# PowerMngt.net
KiCad netlist of a schematic drawn in Altium Designer
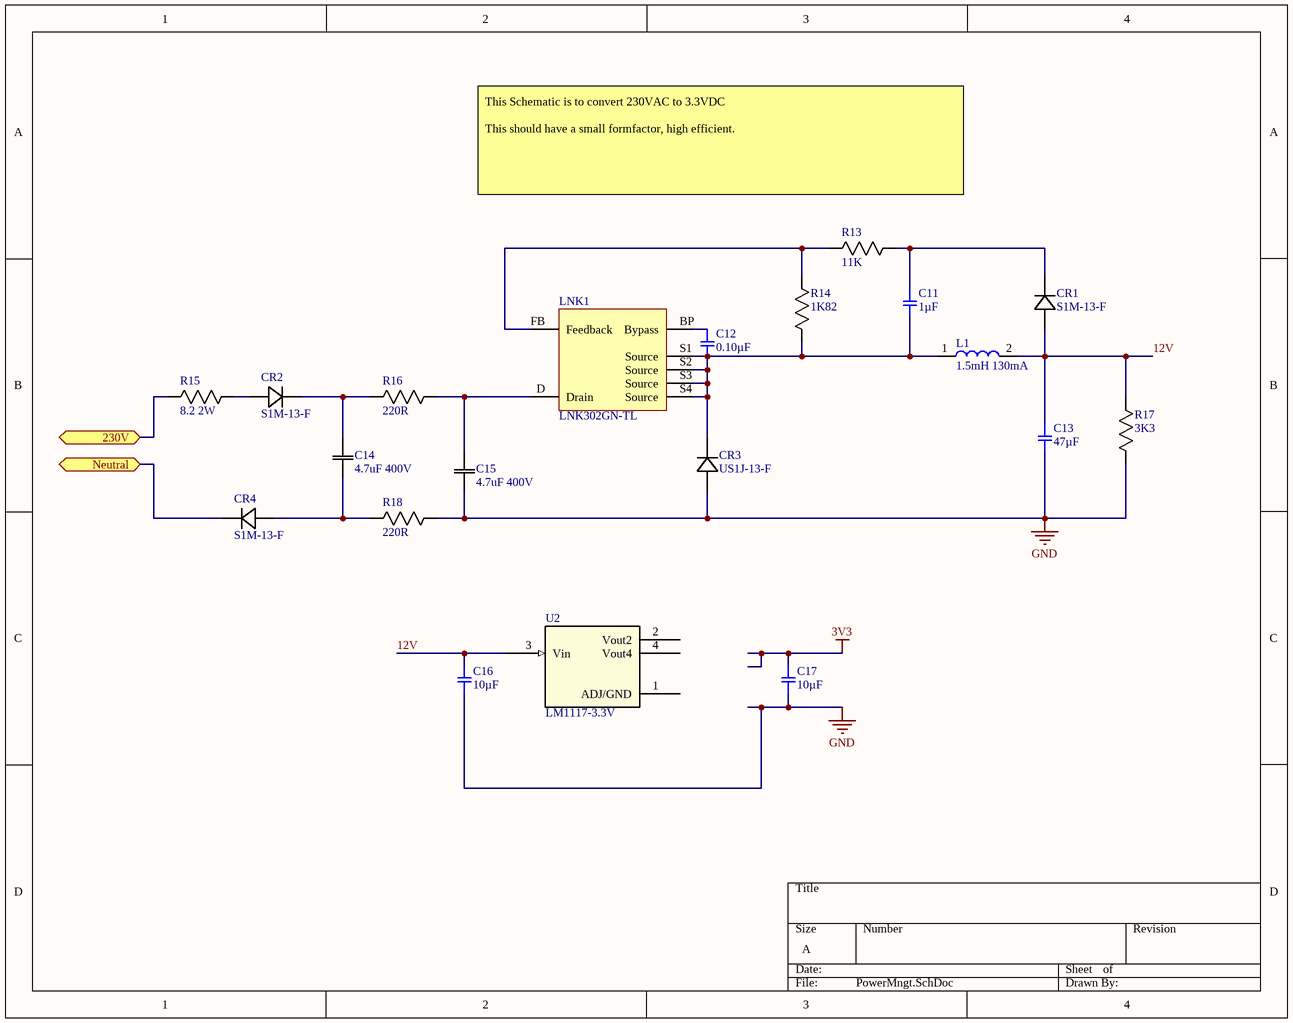
[diagram p0: PowerMngt.SchDoc]

(export (version "E")
  (design (tool "Eeschema 10.0.6"))
  (components
    (comp (ref "C11")
      (value "1µF")
      (footprint "SMD-0603C")
      (description "CAP CER 1UF 16V X5R 0603")
      (fields
        (field (name "DIGI-KEY PART NUMBER") "490-10480-1-ND")
        (field (name "PART NUMBER") "GRM188R61C105MA12D")
      )
      (libsource (lib "Capacitors") (part "GRM188R61C105MA12D"))
    )
    (comp (ref "C12")
      (value "0.10µF")
      (footprint "SMD-0402C")
      (description "CAP CER 0.1UF 16V X7R 0402")
      (fields
        (field (name "DIGI-KEY PART NUMBER") "490-4759-1-ND")
        (field (name "PART NUMBER") "GCM155R71C104KA55D")
      )
      (libsource (lib "Capacitors") (part "GCM155R71C104KA55D"))
    )
    (comp (ref "C13")
      (value "47µF")
      (footprint "SMD-1210C")
      (description "CAP CER 47UF 16V X6S 1210")
      (fields
        (field (name "DIGI-KEY PART NUMBER") "490-10531-1-ND")
        (field (name "PART NUMBER") "GRM32EC81C476KE15L")
      )
      (libsource (lib "Capacitors") (part "GRM32EC81C476KE15L"))
    )
    (comp (ref "C14")
      (value "4.7uF 400V")
      (footprint "CAP_PAN_EEE_G17")
      (description "Imported")
      (fields (field (name "MANUFACTURER_PART_NUMBER") "EEV-EB2G4R7Q"))
      (libsource (lib "XBeeLight") (part "EEV-EB2G4R7Q"))
    )
    (comp (ref "C15")
      (value "4.7uF 400V")
      (footprint "CAP_PAN_EEE_G17")
      (description "Imported")
      (fields (field (name "MANUFACTURER_PART_NUMBER") "EEV-EB2G4R7Q"))
      (libsource (lib "XBeeLight") (part "EEV-EB2G4R7Q"))
    )
    (comp (ref "C16")
      (value "10µF")
      (footprint "SMD-0603C")
      (description "CAP CER 10UF 6.3V X5R 0603")
      (fields
        (field (name "DIGI-KEY PART NUMBER") "490-12538-1-ND")
        (field (name "PART NUMBER") "GRM188R60J106KE47D")
      )
      (libsource (lib "Capacitors") (part "GRM188R60J106KE47D"))
    )
    (comp (ref "C17")
      (value "10µF")
      (footprint "SMD-0603C")
      (description "CAP CER 10UF 6.3V X5R 0603")
      (fields
        (field (name "DIGI-KEY PART NUMBER") "490-12538-1-ND")
        (field (name "PART NUMBER") "GRM188R60J106KE47D")
      )
      (libsource (lib "Capacitors") (part "GRM188R60J106KE47D"))
    )
    (comp (ref "CR1")
      (value "S1M-13-F")
      (footprint "SMA")
      (description "Imported")
      (libsource (lib "XBeeLight") (part "S1M-13-F"))
    )
    (comp (ref "CR2")
      (value "S1M-13-F")
      (footprint "SMA")
      (description "Imported")
      (libsource (lib "XBeeLight") (part "S1M-13-F"))
    )
    (comp (ref "CR3")
      (value "US1J-13-F")
      (footprint "SMA")
      (description "Imported")
      (libsource (lib "XBeeLight") (part "US1J-13-F"))
    )
    (comp (ref "CR4")
      (value "S1M-13-F")
      (footprint "SMA")
      (description "Imported")
      (libsource (lib "XBeeLight") (part "S1M-13-F"))
    )
    (comp (ref "L1")
      (value "1.5mH 130mA")
      (footprint "AIAP-01")
      (description "Imported")
      (fields (field (name "MANUFACTURER_PART_NUMBER") "AIAP-01-152K-T"))
      (libsource (lib "XBeeLight") (part "AIAP-01-152K-T"))
    )
    (comp (ref "LNK1")
      (value "LNK302GN-TL")
      (footprint "SMD-8B")
      (description "IC OFFLINE SWIT OCP 8SMD")
      (fields (field (name "MANUFACTURER") "Power Integrations"))
      (libsource (lib "XBeeLight") (part "LNK302GN-TL"))
    )
    (comp (ref "R13")
      (value "11K")
      (footprint "RC0805N")
      (description "Imported")
      (fields (field (name "MANUFACTURER_PART_NUMBER") "ERA-6AEB113V"))
      (libsource (lib "XBeeLight") (part "ERA-6AEB113V"))
    )
    (comp (ref "R14")
      (value "1K82")
      (footprint "RES_ERA6A_0805")
      (description "Imported")
      (fields (field (name "MANUFACTURER_PART_NUMBER") "ERA-6AEB1821V"))
      (libsource (lib "XBeeLight") (part "ERA-6AEB1821V"))
    )
    (comp (ref "R15")
      (value "8.2 2W")
      (footprint "RES_SMF2_TYCO")
      (description "Imported")
      (fields (field (name "MANUFACTURER_PART_NUMBER") "SMW28R2JT"))
      (libsource (lib "XBeeLight") (part "SMW28R2JT"))
    )
    (comp (ref "R16")
      (value "220R")
      (footprint "RC0805N")
      (description "Imported")
      (fields (field (name "MANUFACTURER_PART_NUMBER") "ERJ-P06J221V"))
      (libsource (lib "XBeeLight") (part "ERJ-P06J221V"))
    )
    (comp (ref "R17")
      (value "3K3")
      (footprint "RC0805N")
      (description "Imported")
      (fields (field (name "MANUFACTURER_PART_NUMBER") "ERA-6AEB332V"))
      (libsource (lib "XBeeLight") (part "ERA-6AEB332V"))
    )
    (comp (ref "R18")
      (value "220R")
      (footprint "RC0805N")
      (description "Imported")
      (fields (field (name "MANUFACTURER_PART_NUMBER") "ERJ-P06J221V"))
      (libsource (lib "XBeeLight") (part "ERJ-P06J221V"))
    )
    (comp (ref "U2")
      (value "LM1117-3.3V")
      (footprint "MP04A")
      (description "Imported")
      (fields (field (name "MANUFACTURER_PART_NUMBER") "LM1117MPX-3.3/NOPB"))
      (libsource (lib "XBee") (part "LM1117MPX-3.3/NO"))
    )
  )
  (nets
    (net (code "1") (name "/12V") (class "Default")
      (node (ref "C13") (pin "1") (pinfunction "1_1") (pintype "passive"))
      (node (ref "C16") (pin "2") (pinfunction "2_2") (pintype "passive"))
      (node (ref "CR1") (pin "2") (pinfunction "2_2") (pintype "passive"))
      (node (ref "L1") (pin "2") (pinfunction "2_2") (pintype "passive"))
      (node (ref "R17") (pin "1") (pinfunction "1_1") (pintype "passive"))
      (node (ref "U2") (pin "3") (pinfunction "Vin_3") (pintype "input"))
    )
    (net (code "2") (name "/230V") (class "Default")
      (node (ref "R15") (pin "2") (pinfunction "2_2") (pintype "passive"))
    )
    (net (code "3") (name "/Neutral") (class "Default")
      (node (ref "CR4") (pin "1") (pinfunction "1_1") (pintype "passive"))
    )
    (net (code "4") (name "3V3") (class "Default")
      (node (ref "C17") (pin "2") (pinfunction "2_2") (pintype "passive"))
    )
    (net (code "5") (name "GND") (class "Default")
      (node (ref "C13") (pin "2") (pinfunction "2_2") (pintype "passive"))
      (node (ref "C15") (pin "1") (pinfunction "1_1") (pintype "passive"))
      (node (ref "C16") (pin "1") (pinfunction "1_1") (pintype "passive"))
      (node (ref "C17") (pin "1") (pinfunction "1_1") (pintype "passive"))
      (node (ref "CR3") (pin "2") (pinfunction "2_2") (pintype "passive"))
      (node (ref "R17") (pin "2") (pinfunction "2_2") (pintype "passive"))
      (node (ref "R18") (pin "1") (pinfunction "1_1") (pintype "passive"))
    )
    (net (code "6") (name "Net-(C11-Pad1)") (class "Default")
      (node (ref "C11") (pin "1") (pinfunction "1_1") (pintype "passive"))
      (node (ref "CR1") (pin "1") (pinfunction "1_1") (pintype "passive"))
      (node (ref "R13") (pin "1") (pinfunction "1_1") (pintype "passive"))
    )
    (net (code "7") (name "Net-(C11-Pad2)") (class "Default")
      (node (ref "C11") (pin "2") (pinfunction "2_2") (pintype "passive"))
      (node (ref "C12") (pin "2") (pinfunction "2_2") (pintype "passive"))
      (node (ref "CR3") (pin "1") (pinfunction "1_1") (pintype "passive"))
      (node (ref "L1") (pin "1") (pinfunction "1_1") (pintype "passive"))
      (node (ref "LNK1") (pin "S1") (pinfunction "Source_S1") (pintype "open_collector"))
      (node (ref "LNK1") (pin "S2") (pinfunction "Source_S2") (pintype "open_collector"))
      (node (ref "LNK1") (pin "S3") (pinfunction "Source_S3") (pintype "open_collector"))
      (node (ref "LNK1") (pin "S4") (pinfunction "Source_S4") (pintype "open_collector"))
      (node (ref "R14") (pin "2") (pinfunction "2_2") (pintype "passive"))
    )
    (net (code "8") (name "Net-(C14-Pad1)") (class "Default")
      (node (ref "C14") (pin "1") (pinfunction "1_1") (pintype "passive"))
      (node (ref "CR4") (pin "2") (pinfunction "2_2") (pintype "passive"))
      (node (ref "R18") (pin "2") (pinfunction "2_2") (pintype "passive"))
    )
    (net (code "9") (name "Net-(C14-Pad2)") (class "Default")
      (node (ref "C14") (pin "2") (pinfunction "2_2") (pintype "passive"))
      (node (ref "CR2") (pin "1") (pinfunction "1_1") (pintype "passive"))
      (node (ref "R16") (pin "2") (pinfunction "2_2") (pintype "passive"))
    )
    (net (code "10") (name "Net-(CR2-Pad2)") (class "Default")
      (node (ref "CR2") (pin "2") (pinfunction "2_2") (pintype "passive"))
      (node (ref "R15") (pin "1") (pinfunction "1_1") (pintype "passive"))
    )
    (net (code "11") (name "Net-(LNK1-Bypass)") (class "Default")
      (node (ref "C12") (pin "1") (pinfunction "1_1") (pintype "passive"))
      (node (ref "LNK1") (pin "BP") (pinfunction "Bypass_BP") (pintype "open_collector"))
    )
    (net (code "12") (name "Net-(LNK1-Drain)") (class "Default")
      (node (ref "C15") (pin "2") (pinfunction "2_2") (pintype "passive"))
      (node (ref "LNK1") (pin "D") (pinfunction "Drain_D") (pintype "open_collector"))
      (node (ref "R16") (pin "1") (pinfunction "1_1") (pintype "passive"))
    )
    (net (code "13") (name "Net-(LNK1-Feedback)") (class "Default")
      (node (ref "LNK1") (pin "FB") (pinfunction "Feedback_FB") (pintype "open_collector"))
      (node (ref "R13") (pin "2") (pinfunction "2_2") (pintype "passive"))
      (node (ref "R14") (pin "1") (pinfunction "1_1") (pintype "passive"))
    )
    (net (code "14") (name "unconnected-(U2-ADJ{slash}GND-Pad1)") (class "Default")
      (node (ref "U2") (pin "1") (pinfunction "ADJ/GND_1") (pintype "passive"))
    )
    (net (code "15") (name "unconnected-(U2-Vout2-Pad2)") (class "Default")
      (node (ref "U2") (pin "2") (pinfunction "Vout2_2") (pintype "power_in"))
    )
    (net (code "16") (name "unconnected-(U2-Vout4-Pad4)") (class "Default")
      (node (ref "U2") (pin "4") (pinfunction "Vout4_4") (pintype "power_in"))
    )
  )
)
